# spotmicrojetson.net
KiCad netlist of a schematic drawn in EAGLE
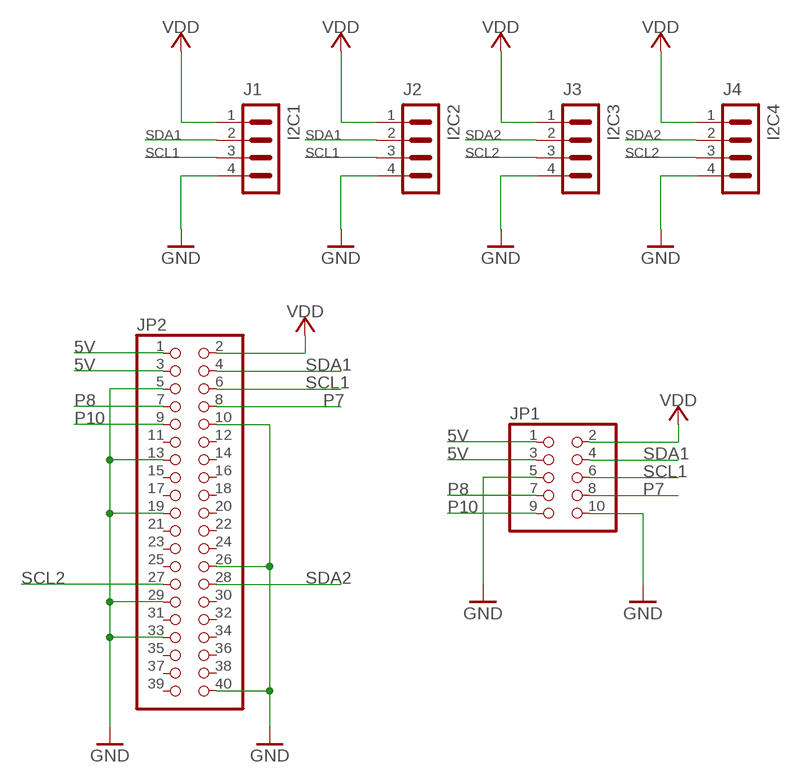
[diagram p0: schematic, sheet 1]

(export (version "E")
  (design (tool "Eeschema 10.0.6"))
  (components
    (comp (ref "J1")
      (value "I2C1")
      (footprint "eagle-import:CON_JST_B4B-PH-SM4-TB(LF)(SN)")
      (libsource (lib "eagle-import") (part "CON_HEADER_1X04_JST_B4B-PH-SM4-TB(LF)(SN)"))
    )
    (comp (ref "J2")
      (value "I2C2")
      (footprint "eagle-import:CON_JST_B4B-PH-SM4-TB(LF)(SN)")
      (libsource (lib "eagle-import") (part "CON_HEADER_1X04_JST_B4B-PH-SM4-TB(LF)(SN)"))
    )
    (comp (ref "J3")
      (value "I2C3")
      (footprint "eagle-import:CON_JST_B4B-PH-SM4-TB(LF)(SN)")
      (libsource (lib "eagle-import") (part "CON_HEADER_1X04_JST_B4B-PH-SM4-TB(LF)(SN)"))
    )
    (comp (ref "J4")
      (value "I2C4")
      (footprint "eagle-import:CON_JST_B4B-PH-SM4-TB(LF)(SN)")
      (libsource (lib "eagle-import") (part "CON_HEADER_1X04_JST_B4B-PH-SM4-TB(LF)(SN)"))
    )
    (comp (ref "JP1")
      (value "PINHD-2X5SMT")
      (footprint "eagle-import:2X05_SMT")
      (libsource (lib "eagle-import") (part "PINHD-2X5SMT"))
    )
    (comp (ref "JP2")
      (value "PINHD-2X20SMT")
      (footprint "eagle-import:2X20_SMT")
      (libsource (lib "eagle-import") (part "PINHD-2X20SMT"))
    )
  )
  (nets
    (net (code "1") (name "/5V") (class "Default")
      (node (ref "JP1") (pin "1") (pinfunction "1_1") (pintype "passive"))
      (node (ref "JP1") (pin "3") (pinfunction "3_3") (pintype "passive"))
      (node (ref "JP2") (pin "1") (pinfunction "1_1") (pintype "passive"))
      (node (ref "JP2") (pin "3") (pinfunction "3_3") (pintype "passive"))
    )
    (net (code "2") (name "/P7") (class "Default")
      (node (ref "JP1") (pin "8") (pinfunction "8_8") (pintype "passive"))
      (node (ref "JP2") (pin "8") (pinfunction "8_8") (pintype "passive"))
    )
    (net (code "3") (name "/P8") (class "Default")
      (node (ref "JP1") (pin "7") (pinfunction "7_7") (pintype "passive"))
      (node (ref "JP2") (pin "7") (pinfunction "7_7") (pintype "passive"))
    )
    (net (code "4") (name "/P10") (class "Default")
      (node (ref "JP1") (pin "9") (pinfunction "9_9") (pintype "passive"))
      (node (ref "JP2") (pin "9") (pinfunction "9_9") (pintype "passive"))
    )
    (net (code "5") (name "/SCL1") (class "Default")
      (node (ref "J1") (pin "3") (pinfunction "3_3") (pintype "bidirectional"))
      (node (ref "J2") (pin "3") (pinfunction "3_3") (pintype "bidirectional"))
      (node (ref "JP1") (pin "6") (pinfunction "6_6") (pintype "passive"))
      (node (ref "JP2") (pin "6") (pinfunction "6_6") (pintype "passive"))
    )
    (net (code "6") (name "/SCL2") (class "Default")
      (node (ref "J3") (pin "3") (pinfunction "3_3") (pintype "bidirectional"))
      (node (ref "J4") (pin "3") (pinfunction "3_3") (pintype "bidirectional"))
      (node (ref "JP2") (pin "27") (pinfunction "27_27") (pintype "passive"))
    )
    (net (code "7") (name "/SDA1") (class "Default")
      (node (ref "J1") (pin "2") (pinfunction "2_2") (pintype "bidirectional"))
      (node (ref "J2") (pin "2") (pinfunction "2_2") (pintype "bidirectional"))
      (node (ref "JP1") (pin "4") (pinfunction "4_4") (pintype "passive"))
      (node (ref "JP2") (pin "4") (pinfunction "4_4") (pintype "passive"))
    )
    (net (code "8") (name "/SDA2") (class "Default")
      (node (ref "J3") (pin "2") (pinfunction "2_2") (pintype "bidirectional"))
      (node (ref "J4") (pin "2") (pinfunction "2_2") (pintype "bidirectional"))
      (node (ref "JP2") (pin "28") (pinfunction "28_28") (pintype "passive"))
    )
    (net (code "9") (name "GND") (class "Default")
      (node (ref "J1") (pin "4") (pinfunction "4_4") (pintype "bidirectional"))
      (node (ref "J2") (pin "4") (pinfunction "4_4") (pintype "bidirectional"))
      (node (ref "J3") (pin "4") (pinfunction "4_4") (pintype "bidirectional"))
      (node (ref "J4") (pin "4") (pinfunction "4_4") (pintype "bidirectional"))
      (node (ref "JP1") (pin "10") (pinfunction "10_10") (pintype "passive"))
      (node (ref "JP1") (pin "5") (pinfunction "5_5") (pintype "passive"))
      (node (ref "JP2") (pin "10") (pinfunction "10_10") (pintype "passive"))
      (node (ref "JP2") (pin "13") (pinfunction "13_13") (pintype "passive"))
      (node (ref "JP2") (pin "19") (pinfunction "19_19") (pintype "passive"))
      (node (ref "JP2") (pin "26") (pinfunction "26_26") (pintype "passive"))
      (node (ref "JP2") (pin "29") (pinfunction "29_29") (pintype "passive"))
      (node (ref "JP2") (pin "33") (pinfunction "33_33") (pintype "passive"))
      (node (ref "JP2") (pin "40") (pinfunction "40_40") (pintype "passive"))
      (node (ref "JP2") (pin "5") (pinfunction "5_5") (pintype "passive"))
    )
    (net (code "10") (name "VDD") (class "Default")
      (node (ref "J1") (pin "1") (pinfunction "1_1") (pintype "bidirectional"))
      (node (ref "J2") (pin "1") (pinfunction "1_1") (pintype "bidirectional"))
      (node (ref "J3") (pin "1") (pinfunction "1_1") (pintype "bidirectional"))
      (node (ref "J4") (pin "1") (pinfunction "1_1") (pintype "bidirectional"))
      (node (ref "JP1") (pin "2") (pinfunction "2_2") (pintype "passive"))
      (node (ref "JP2") (pin "2") (pinfunction "2_2") (pintype "passive"))
    )
    (net (code "11") (name "unconnected-(JP2-Pad11)") (class "Default")
      (node (ref "JP2") (pin "11") (pinfunction "11_11") (pintype "passive"))
    )
    (net (code "12") (name "unconnected-(JP2-Pad12)") (class "Default")
      (node (ref "JP2") (pin "12") (pinfunction "12_12") (pintype "passive"))
    )
    (net (code "13") (name "unconnected-(JP2-Pad14)") (class "Default")
      (node (ref "JP2") (pin "14") (pinfunction "14_14") (pintype "passive"))
    )
    (net (code "14") (name "unconnected-(JP2-Pad15)") (class "Default")
      (node (ref "JP2") (pin "15") (pinfunction "15_15") (pintype "passive"))
    )
    (net (code "15") (name "unconnected-(JP2-Pad16)") (class "Default")
      (node (ref "JP2") (pin "16") (pinfunction "16_16") (pintype "passive"))
    )
    (net (code "16") (name "unconnected-(JP2-Pad17)") (class "Default")
      (node (ref "JP2") (pin "17") (pinfunction "17_17") (pintype "passive"))
    )
    (net (code "17") (name "unconnected-(JP2-Pad18)") (class "Default")
      (node (ref "JP2") (pin "18") (pinfunction "18_18") (pintype "passive"))
    )
    (net (code "18") (name "unconnected-(JP2-Pad20)") (class "Default")
      (node (ref "JP2") (pin "20") (pinfunction "20_20") (pintype "passive"))
    )
    (net (code "19") (name "unconnected-(JP2-Pad21)") (class "Default")
      (node (ref "JP2") (pin "21") (pinfunction "21_21") (pintype "passive"))
    )
    (net (code "20") (name "unconnected-(JP2-Pad22)") (class "Default")
      (node (ref "JP2") (pin "22") (pinfunction "22_22") (pintype "passive"))
    )
    (net (code "21") (name "unconnected-(JP2-Pad23)") (class "Default")
      (node (ref "JP2") (pin "23") (pinfunction "23_23") (pintype "passive"))
    )
    (net (code "22") (name "unconnected-(JP2-Pad24)") (class "Default")
      (node (ref "JP2") (pin "24") (pinfunction "24_24") (pintype "passive"))
    )
    (net (code "23") (name "unconnected-(JP2-Pad25)") (class "Default")
      (node (ref "JP2") (pin "25") (pinfunction "25_25") (pintype "passive"))
    )
    (net (code "24") (name "unconnected-(JP2-Pad30)") (class "Default")
      (node (ref "JP2") (pin "30") (pinfunction "30_30") (pintype "passive"))
    )
    (net (code "25") (name "unconnected-(JP2-Pad31)") (class "Default")
      (node (ref "JP2") (pin "31") (pinfunction "31_31") (pintype "passive"))
    )
    (net (code "26") (name "unconnected-(JP2-Pad32)") (class "Default")
      (node (ref "JP2") (pin "32") (pinfunction "32_32") (pintype "passive"))
    )
    (net (code "27") (name "unconnected-(JP2-Pad34)") (class "Default")
      (node (ref "JP2") (pin "34") (pinfunction "34_34") (pintype "passive"))
    )
    (net (code "28") (name "unconnected-(JP2-Pad35)") (class "Default")
      (node (ref "JP2") (pin "35") (pinfunction "35_35") (pintype "passive"))
    )
    (net (code "29") (name "unconnected-(JP2-Pad36)") (class "Default")
      (node (ref "JP2") (pin "36") (pinfunction "36_36") (pintype "passive"))
    )
    (net (code "30") (name "unconnected-(JP2-Pad37)") (class "Default")
      (node (ref "JP2") (pin "37") (pinfunction "37_37") (pintype "passive"))
    )
    (net (code "31") (name "unconnected-(JP2-Pad38)") (class "Default")
      (node (ref "JP2") (pin "38") (pinfunction "38_38") (pintype "passive"))
    )
    (net (code "32") (name "unconnected-(JP2-Pad39)") (class "Default")
      (node (ref "JP2") (pin "39") (pinfunction "39_39") (pintype "passive"))
    )
  )
)
